# microcontroller.net
KiCad netlist of a schematic drawn in Altium Designer
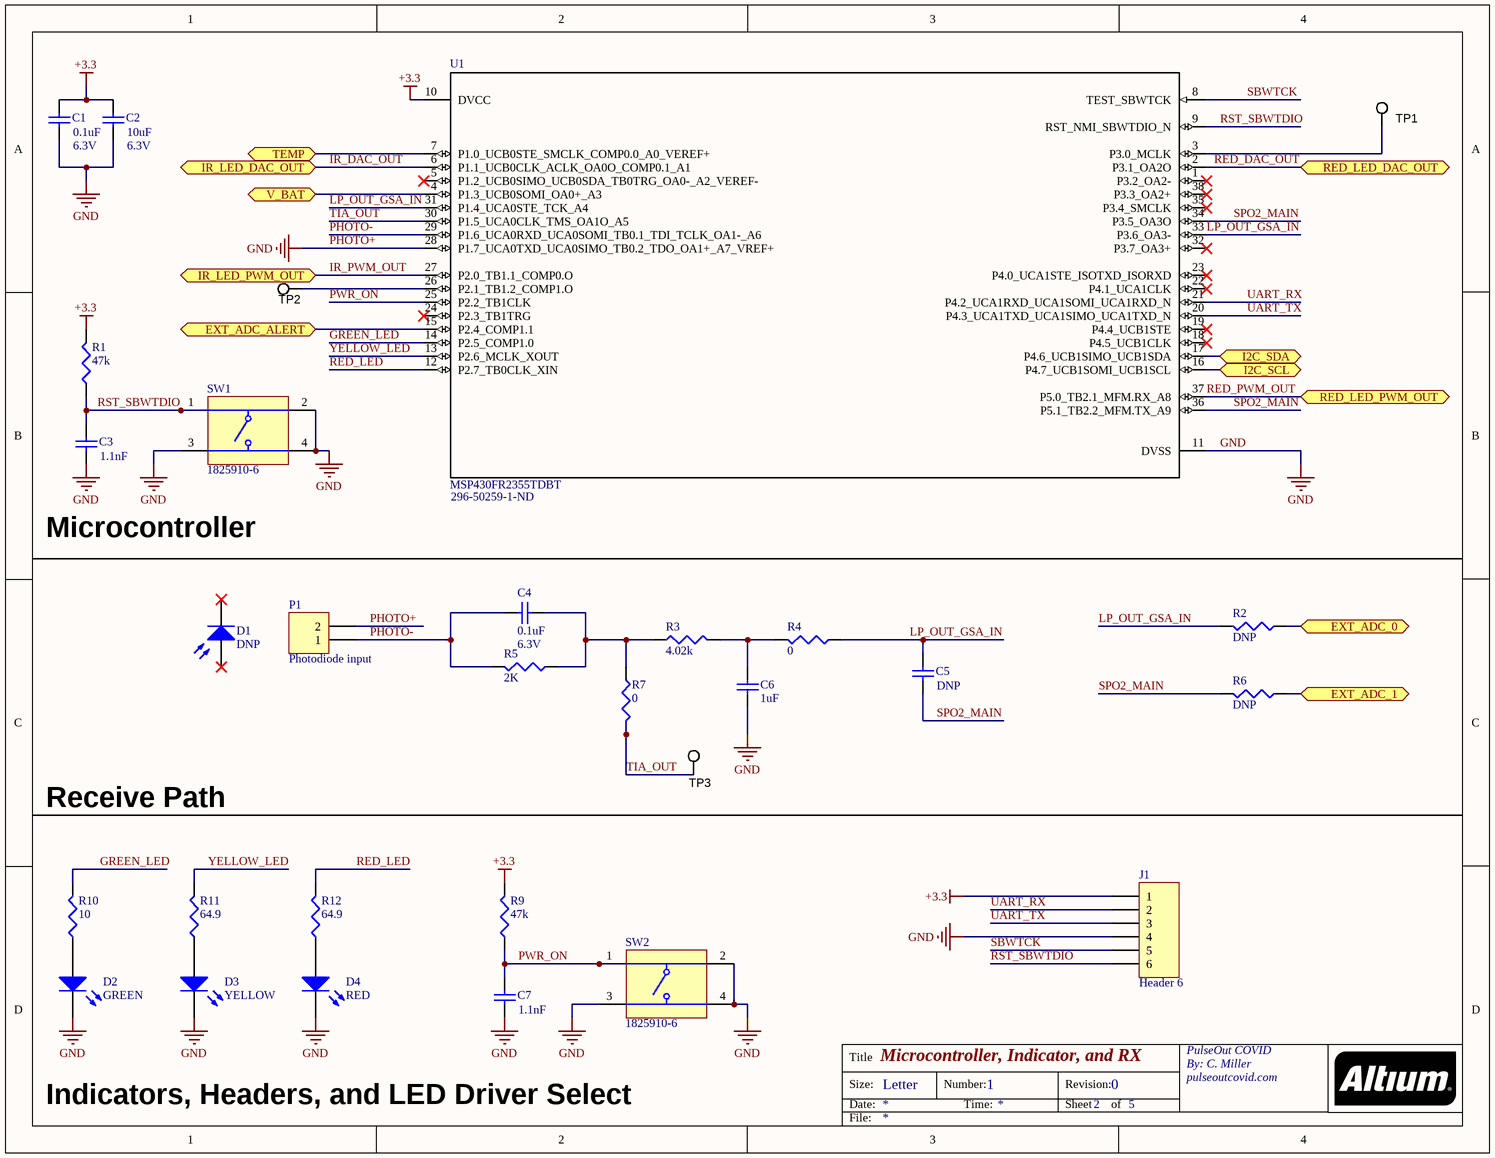
[diagram p0: microcontroller.SchDoc]

(export (version "E")
  (design (tool "Eeschema 10.0.6"))
  (components
    (comp (ref "C1")
      (value "0.1uF")
      (footprint "1608[0603]")
      (description "Capacitor (Semiconductor SIM Model)")
      (fields
        (field (name "VOLTAGE") "6.3V")
        (field (name "MPN") "06036C104KAT4A")
        (field (name "MANUFACTURER") "AVX Corporation")
        (field (name "PUBLISHER") "Altium Limited")
      )
      (libsource (lib "Miscellaneous Devices") (part "Cap Semi"))
    )
    (comp (ref "C2")
      (value "10uF")
      (footprint "1608[0603]")
      (description "Capacitor (Semiconductor SIM Model)")
      (fields
        (field (name "VOLTAGE") "6.3V")
        (field (name "MPN") "JMK107ABJ106KA-T")
        (field (name "MANUFACTURER") "Taiyo Yuden")
        (field (name "PUBLISHER") "Altium Limited")
      )
      (libsource (lib "Miscellaneous Devices") (part "Cap Semi"))
    )
    (comp (ref "C3")
      (value "1.1nF")
      (footprint "0603")
      (description "Capacitor (Semiconductor SIM Model)")
      (fields
        (field (name "MPN") "GRM1885C1H112JA01D")
        (field (name "MANUFACTURER") "Murata Electronics")
        (field (name "PUBLISHER") "Altium Limited")
      )
      (libsource (lib "Miscellaneous Devices") (part "Cap Semi"))
    )
    (comp (ref "C4")
      (value "0.1uF")
      (footprint "1608[0603]")
      (description "Capacitor (Semiconductor SIM Model)")
      (fields
        (field (name "VOLTAGE") "6.3V")
        (field (name "MPN") "06036C104KAT4A")
        (field (name "MANUFACTURER") "AVX Corporation")
        (field (name "PUBLISHER") "Altium Limited")
      )
      (libsource (lib "Miscellaneous Devices") (part "Cap Semi"))
    )
    (comp (ref "C5")
      (value "DNP")
      (footprint "0603")
      (description "Capacitor (Semiconductor SIM Model)")
      (fields (field (name "Comment") "Cap Semi") (field (name "PUBLISHER") "Altium Limited"))
      (libsource (lib "Miscellaneous Devices") (part "Cap Semi"))
    )
    (comp (ref "C6")
      (value "1uF")
      (footprint "1608[0603]")
      (description "Capacitor (Semiconductor SIM Model)")
      (fields
        (field (name "MPN") "C0603X105J9RAC7867")
        (field (name "MANUFACTURER") "KEMET")
        (field (name "PUBLISHER") "Altium Limited")
      )
      (libsource (lib "Miscellaneous Devices") (part "Cap Semi"))
    )
    (comp (ref "C7")
      (value "1.1nF")
      (footprint "0603")
      (description "Capacitor (Semiconductor SIM Model)")
      (fields
        (field (name "MPN") "GRM1885C1H112JA01D")
        (field (name "MANUFACTURER") "Murata Electronics")
        (field (name "PUBLISHER") "Altium Limited")
      )
      (libsource (lib "Miscellaneous Devices") (part "Cap Semi"))
    )
    (comp (ref "D1")
      (value "DNP")
      (footprint "PIN2")
      (description "Photosensitive Diode")
      (fields
        (field (name "MPN") "BPW34")
        (field (name "MANUFACTURER") "OSRAM Opto Semiconductors Inc.")
        (field (name "PUBLISHER") "Altium Limited")
      )
      (libsource (lib "Miscellaneous Devices") (part "Photo Sen"))
    )
    (comp (ref "D2")
      (value "GREEN")
      (footprint "3.5X2.8X1.9")
      (description "Typical BLUE SiC LED")
      (fields
        (field (name "MPN") "150141GS73100")
        (field (name "MANUFACTURER") "Wurth Elektronik")
        (field (name "PUBLISHER") "Altium Limited")
      )
      (libsource (lib "Miscellaneous Devices") (part "LED3"))
    )
    (comp (ref "D3")
      (value "YELLOW")
      (footprint "3.5X2.8X1.9")
      (description "Typical BLUE SiC LED")
      (fields
        (field (name "MPN") "SML-Z14YTT86C")
        (field (name "MANUFACTURER") "Rohm Semiconductor")
        (field (name "PUBLISHER") "Altium Limited")
      )
      (libsource (lib "Miscellaneous Devices") (part "LED3"))
    )
    (comp (ref "D4")
      (value "RED")
      (footprint "3.5X2.8X1.9")
      (description "Typical BLUE SiC LED")
      (fields
        (field (name "MPN") "150141RS73100")
        (field (name "MANUFACTURER") "Wurth Elektronik")
        (field (name "PUBLISHER") "Altium Limited")
      )
      (libsource (lib "Miscellaneous Devices") (part "LED3"))
    )
    (comp (ref "J1")
      (value "Header 6")
      (footprint "HDR1X6")
      (description "Header, 6-Pin")
      (fields
        (field (name "MPN") "800-10-006-10-001000")
        (field (name "MANUFACTURER") "Mill-Max Manufacturing")
        (field (name "PUBLISHER") "Altium Limited")
      )
      (libsource (lib "Miscellaneous Connectors") (part "Header 6"))
    )
    (comp (ref "P1")
      (value "Photodiode input")
      (footprint "HDR1X2")
      (description "Header, 2-Pin")
      (fields (field (name "PUBLISHER") "Altium Limited"))
      (libsource (lib "Miscellaneous Connectors") (part "Header 2"))
    )
    (comp (ref "R1")
      (value "47k")
      (footprint "J1-0603")
      (description "Resistor")
      (fields
        (field (name "MPN") "RC0603JR-0747KL")
        (field (name "MANUFACTURER") "Yageo")
        (field (name "PUBLISHER") "Altium Limited")
      )
      (libsource (lib "Miscellaneous Devices") (part "Res3"))
    )
    (comp (ref "R2")
      (value "DNP")
      (footprint "J1-0603")
      (description "Resistor")
      (fields (field (name "Comment") "Res3") (field (name "PUBLISHER") "Altium Limited"))
      (libsource (lib "Miscellaneous Devices") (part "Res3"))
    )
    (comp (ref "R3")
      (value "4.02k")
      (footprint "J1-0603")
      (description "Resistor")
      (fields
        (field (name "MPN") "RMCF0603FT4K02")
        (field (name "MANUFACTURER") "Stackpole Electronics")
        (field (name "PUBLISHER") "Altium Limited")
      )
      (libsource (lib "Miscellaneous Devices") (part "Res3"))
    )
    (comp (ref "R4")
      (value "0")
      (footprint "J1-0603")
      (description "Resistor")
      (fields
        (field (name "MPN") "RC0603JR-070RL")
        (field (name "MANUFACTURER") "Yageo")
        (field (name "PUBLISHER") "Altium Limited")
      )
      (libsource (lib "Miscellaneous Devices") (part "Res3"))
    )
    (comp (ref "R5")
      (value "2K")
      (footprint "J1-0603")
      (description "Resistor")
      (fields
        (field (name "MPN") "RC0603FR-072KL")
        (field (name "MANUFACTURER") "Yageo")
        (field (name "PUBLISHER") "Altium Limited")
      )
      (libsource (lib "Miscellaneous Devices") (part "Res3"))
    )
    (comp (ref "R6")
      (value "DNP")
      (footprint "J1-0603")
      (description "Resistor")
      (fields (field (name "Comment") "Res3") (field (name "PUBLISHER") "Altium Limited"))
      (libsource (lib "Miscellaneous Devices") (part "Res3"))
    )
    (comp (ref "R7")
      (value "0")
      (footprint "J1-0603")
      (description "Resistor")
      (fields
        (field (name "MPN") "RC0603JR-070RL")
        (field (name "MANUFACTURER") "Yageo")
        (field (name "PUBLISHER") "Altium Limited")
      )
      (libsource (lib "Miscellaneous Devices") (part "Res3"))
    )
    (comp (ref "R9")
      (value "47k")
      (footprint "J1-0603")
      (description "Resistor")
      (fields
        (field (name "MPN") "RC0603JR-0747KL")
        (field (name "MANUFACTURER") "Yageo")
        (field (name "PUBLISHER") "Altium Limited")
      )
      (libsource (lib "Miscellaneous Devices") (part "Res3"))
    )
    (comp (ref "R10")
      (value "10")
      (footprint "J1-0603")
      (description "Resistor")
      (fields
        (field (name "MPN") "RC0603FR-0710RL")
        (field (name "MANUFACTURER") "Yageo")
        (field (name "PUBLISHER") "Altium Limited")
      )
      (libsource (lib "Miscellaneous Devices") (part "Res3"))
    )
    (comp (ref "R11")
      (value "64.9")
      (footprint "J1-0603")
      (description "Resistor")
      (fields
        (field (name "MPN") "ERA-3AEB64R9V")
        (field (name "MANUFACTURER") "Panasonic")
        (field (name "PUBLISHER") "Altium Limited")
      )
      (libsource (lib "Miscellaneous Devices") (part "Res3"))
    )
    (comp (ref "R12")
      (value "64.9")
      (footprint "J1-0603")
      (description "Resistor")
      (fields
        (field (name "MPN") "ERA-3AEB64R9V")
        (field (name "MANUFACTURER") "Panasonic")
        (field (name "PUBLISHER") "Altium Limited")
      )
      (libsource (lib "Miscellaneous Devices") (part "Res3"))
    )
    (comp (ref "SW1")
      (value "1825910-6")
      (footprint "TECO-1825910-6_V")
      (description "Tact Switch, SPST-NO, 0.05 A, -35 to 85 degC, 4-Pin THD, RoHS, Bulk")
      (fields (field (name "MANUFACTURER") "TE Connectivity"))
      (libsource (lib "Altium Content Vault") (part "SW-SPST-4_A"))
    )
    (comp (ref "SW2")
      (value "1825910-6")
      (footprint "TECO-1825910-6_V")
      (description "Tact Switch, SPST-NO, 0.05 A, -35 to 85 degC, 4-Pin THD, RoHS, Bulk")
      (fields (field (name "MANUFACTURER") "TE Connectivity"))
      (libsource (lib "Altium Content Vault") (part "SW-SPST-4_A"))
    )
    (comp (ref "TP1")
      (value "5002")
      (footprint "Keystone5002")
      (description "Test Point, Miniature, White, TH")
      (fields (field (name "MANUFACTURER") "Keystone") (field (name "PUBLISHER") "Texas Instruments"))
      (libsource (lib "MDBU017A") (part "5002"))
    )
    (comp (ref "TP2")
      (value "5002")
      (footprint "Keystone5002")
      (description "Test Point, Miniature, White, TH")
      (fields (field (name "MANUFACTURER") "Keystone") (field (name "PUBLISHER") "Texas Instruments"))
      (libsource (lib "MDBU017A") (part "5002"))
    )
    (comp (ref "TP3")
      (value "5002")
      (footprint "Keystone5002")
      (description "Test Point, Miniature, White, TH")
      (fields (field (name "MANUFACTURER") "Keystone") (field (name "PUBLISHER") "Texas Instruments"))
      (libsource (lib "MDBU017A") (part "5002"))
    )
    (comp (ref "U1")
      (value "MSP430FR2355TDBT")
      (footprint "DBT0038A_N")
      (description "MSP430 IC")
      (fields
        (field (name "MANUFACTURER") "Texas Instruments")
        (field (name "PARTNUMBER") "MSP430FR2355IDBT")
        (field (name "DIGIKEY") "296-50259-1-ND")
        (field (name "COPYRIGHT") "Copyright (C) 2018 Accelerated Designs. All rights reserved")
      )
      (libsource (lib "CustomLib") (part "MSP430FR2355TDBT"))
    )
  )
  (nets
    (net (code "1") (name "+3.3") (class "Default")
      (node (ref "C1") (pin "2") (pinfunction "2_2") (pintype "passive"))
      (node (ref "C2") (pin "2") (pinfunction "2_2") (pintype "passive"))
      (node (ref "J1") (pin "1") (pinfunction "1_1") (pintype "passive"))
      (node (ref "R1") (pin "2") (pinfunction "2_2") (pintype "passive"))
      (node (ref "R9") (pin "2") (pinfunction "2_2") (pintype "passive"))
      (node (ref "U1") (pin "10") (pinfunction "DVCC_10") (pintype "power_in"))
    )
    (net (code "2") (name "/EXT_ADC_0") (class "Default")
      (node (ref "R2") (pin "1") (pinfunction "1_1") (pintype "passive"))
    )
    (net (code "3") (name "/EXT_ADC_1") (class "Default")
      (node (ref "R6") (pin "1") (pinfunction "1_1") (pintype "passive"))
    )
    (net (code "4") (name "/EXT_ADC_ALERT") (class "Default")
      (node (ref "U1") (pin "15") (pinfunction "P2.4_COMP1.1_15") (pintype "bidirectional"))
    )
    (net (code "5") (name "/GREEN_LED") (class "Default")
      (node (ref "R10") (pin "2") (pinfunction "2_2") (pintype "passive"))
      (node (ref "U1") (pin "14") (pinfunction "P2.5_COMP1.0_14") (pintype "bidirectional"))
    )
    (net (code "6") (name "/I2C_SCL") (class "Default")
      (node (ref "U1") (pin "16") (pinfunction "P4.7_UCB1SOMI_UCB1SCL_16") (pintype "bidirectional"))
    )
    (net (code "7") (name "/I2C_SDA") (class "Default")
      (node (ref "U1") (pin "17") (pinfunction "P4.6_UCB1SIMO_UCB1SDA_17") (pintype "bidirectional"))
    )
    (net (code "8") (name "/IR_DAC_OUT") (class "Default")
      (node (ref "U1") (pin "6") (pinfunction "P1.1_UCB0CLK_ACLK_OA0O_COMP0.1_A1_6") (pintype "bidirectional"))
    )
    (net (code "9") (name "/IR_PWM_OUT") (class "Default")
      (node (ref "U1") (pin "27") (pinfunction "P2.0_TB1.1_COMP0.O_27") (pintype "bidirectional"))
    )
    (net (code "10") (name "/LP_OUT_GSA_IN") (class "Default")
      (node (ref "C5") (pin "2") (pinfunction "2_2") (pintype "passive"))
      (node (ref "R2") (pin "2") (pinfunction "2_2") (pintype "passive"))
      (node (ref "R4") (pin "1") (pinfunction "1_1") (pintype "passive"))
      (node (ref "U1") (pin "31") (pinfunction "P1.4_UCA0STE_TCK_A4_31") (pintype "bidirectional"))
      (node (ref "U1") (pin "33") (pinfunction "P3.6_OA3-_33") (pintype "bidirectional"))
    )
    (net (code "11") (name "/PHOTO-") (class "Default")
      (node (ref "C4") (pin "2") (pinfunction "2_2") (pintype "passive"))
      (node (ref "P1") (pin "1") (pinfunction "1_1") (pintype "passive"))
      (node (ref "R5") (pin "2") (pinfunction "2_2") (pintype "passive"))
      (node (ref "U1") (pin "29") (pinfunction "P1.6_UCA0RXD_UCA0SOMI_TB0.1_TDI_TCLK_OA1-_A6_29") (pintype "bidirectional"))
    )
    (net (code "12") (name "/PWR_ON") (class "Default")
      (node (ref "C7") (pin "2") (pinfunction "2_2") (pintype "passive"))
      (node (ref "R9") (pin "1") (pinfunction "1_1") (pintype "passive"))
      (node (ref "SW2") (pin "1") (pinfunction "1_1") (pintype "passive"))
      (node (ref "U1") (pin "25") (pinfunction "P2.2_TB1CLK_25") (pintype "bidirectional"))
    )
    (net (code "13") (name "/RED_DAC_OUT") (class "Default")
      (node (ref "U1") (pin "2") (pinfunction "P3.1_OA2O_2") (pintype "bidirectional"))
    )
    (net (code "14") (name "/RED_LED") (class "Default")
      (node (ref "R12") (pin "2") (pinfunction "2_2") (pintype "passive"))
      (node (ref "U1") (pin "12") (pinfunction "P2.7_TB0CLK_XIN_12") (pintype "bidirectional"))
    )
    (net (code "15") (name "/RED_PWM_OUT") (class "Default")
      (node (ref "U1") (pin "37") (pinfunction "P5.0_TB2.1_MFM.RX_A8_37") (pintype "bidirectional"))
    )
    (net (code "16") (name "/RST_SBWTDIO") (class "Default")
      (node (ref "C3") (pin "2") (pinfunction "2_2") (pintype "passive"))
      (node (ref "J1") (pin "6") (pinfunction "6_6") (pintype "passive"))
      (node (ref "R1") (pin "1") (pinfunction "1_1") (pintype "passive"))
      (node (ref "SW1") (pin "1") (pinfunction "1_1") (pintype "passive"))
      (node (ref "U1") (pin "9") (pinfunction "RST_NMI_SBWTDIO_N_9") (pintype "bidirectional"))
    )
    (net (code "17") (name "/SBWTCK") (class "Default")
      (node (ref "J1") (pin "5") (pinfunction "5_5") (pintype "passive"))
      (node (ref "U1") (pin "8") (pinfunction "TEST_SBWTCK_8") (pintype "input"))
    )
    (net (code "18") (name "/SPO2_MAIN") (class "Default")
      (node (ref "C5") (pin "1") (pinfunction "1_1") (pintype "passive"))
      (node (ref "R6") (pin "2") (pinfunction "2_2") (pintype "passive"))
      (node (ref "U1") (pin "34") (pinfunction "P3.5_OA3O_34") (pintype "bidirectional"))
      (node (ref "U1") (pin "36") (pinfunction "P5.1_TB2.2_MFM.TX_A9_36") (pintype "bidirectional"))
    )
    (net (code "19") (name "/TEMP") (class "Default")
      (node (ref "U1") (pin "7") (pinfunction "P1.0_UCB0STE_SMCLK_COMP0.0_A0_VEREF+_7") (pintype "bidirectional"))
    )
    (net (code "20") (name "/TIA_OUT") (class "Default")
      (node (ref "R7") (pin "2") (pinfunction "2_2") (pintype "passive"))
      (node (ref "TP3") (pin "1") (pintype "passive"))
      (node (ref "U1") (pin "30") (pinfunction "P1.5_UCA0CLK_TMS_OA1O_A5_30") (pintype "bidirectional"))
    )
    (net (code "21") (name "/UART_RX") (class "Default")
      (node (ref "J1") (pin "2") (pinfunction "2_2") (pintype "passive"))
      (node (ref "U1") (pin "21") (pinfunction "P4.2_UCA1RXD_UCA1SOMI_UCA1RXD_N_21") (pintype "bidirectional"))
    )
    (net (code "22") (name "/UART_TX") (class "Default")
      (node (ref "J1") (pin "3") (pinfunction "3_3") (pintype "passive"))
      (node (ref "U1") (pin "20") (pinfunction "P4.3_UCA1TXD_UCA1SIMO_UCA1TXD_N_20") (pintype "bidirectional"))
    )
    (net (code "23") (name "/V_BAT") (class "Default")
      (node (ref "U1") (pin "4") (pinfunction "P1.3_UCB0SOMI_OA0+_A3_4") (pintype "bidirectional"))
    )
    (net (code "24") (name "/YELLOW_LED") (class "Default")
      (node (ref "R11") (pin "2") (pinfunction "2_2") (pintype "passive"))
      (node (ref "U1") (pin "13") (pinfunction "P2.6_MCLK_XOUT_13") (pintype "bidirectional"))
    )
    (net (code "25") (name "GND") (class "Default")
      (node (ref "C1") (pin "1") (pinfunction "1_1") (pintype "passive"))
      (node (ref "C2") (pin "1") (pinfunction "1_1") (pintype "passive"))
      (node (ref "C3") (pin "1") (pinfunction "1_1") (pintype "passive"))
      (node (ref "C6") (pin "2") (pinfunction "2_2") (pintype "passive"))
      (node (ref "C7") (pin "1") (pinfunction "1_1") (pintype "passive"))
      (node (ref "D2") (pin "2") (pinfunction "K_2") (pintype "passive"))
      (node (ref "D3") (pin "2") (pinfunction "K_2") (pintype "passive"))
      (node (ref "D4") (pin "2") (pinfunction "K_2") (pintype "passive"))
      (node (ref "J1") (pin "4") (pinfunction "4_4") (pintype "passive"))
      (node (ref "P1") (pin "2") (pinfunction "2_2") (pintype "passive"))
      (node (ref "SW1") (pin "2") (pinfunction "2_2") (pintype "passive"))
      (node (ref "SW1") (pin "3") (pinfunction "3_3") (pintype "passive"))
      (node (ref "SW1") (pin "4") (pinfunction "4_4") (pintype "passive"))
      (node (ref "SW2") (pin "2") (pinfunction "2_2") (pintype "passive"))
      (node (ref "SW2") (pin "3") (pinfunction "3_3") (pintype "passive"))
      (node (ref "SW2") (pin "4") (pinfunction "4_4") (pintype "passive"))
      (node (ref "U1") (pin "11") (pinfunction "DVSS_11") (pintype "power_in"))
      (node (ref "U1") (pin "28") (pinfunction "P1.7_UCA0TXD_UCA0SIMO_TB0.2_TDO_OA1+_A7_VREF+_28") (pintype "bidirectional"))
    )
    (net (code "26") (name "Net-(C4-Pad1)") (class "Default")
      (node (ref "C4") (pin "1") (pinfunction "1_1") (pintype "passive"))
      (node (ref "R3") (pin "1") (pinfunction "1_1") (pintype "passive"))
      (node (ref "R5") (pin "1") (pinfunction "1_1") (pintype "passive"))
      (node (ref "R7") (pin "1") (pinfunction "1_1") (pintype "passive"))
    )
    (net (code "27") (name "Net-(C6-Pad1)") (class "Default")
      (node (ref "C6") (pin "1") (pinfunction "1_1") (pintype "passive"))
      (node (ref "R3") (pin "2") (pinfunction "2_2") (pintype "passive"))
      (node (ref "R4") (pin "2") (pinfunction "2_2") (pintype "passive"))
    )
    (net (code "28") (name "Net-(D2-A)") (class "Default")
      (node (ref "D2") (pin "1") (pinfunction "A_1") (pintype "passive"))
      (node (ref "R10") (pin "1") (pinfunction "1_1") (pintype "passive"))
    )
    (net (code "29") (name "Net-(D3-A)") (class "Default")
      (node (ref "D3") (pin "1") (pinfunction "A_1") (pintype "passive"))
      (node (ref "R11") (pin "1") (pinfunction "1_1") (pintype "passive"))
    )
    (net (code "30") (name "Net-(D4-A)") (class "Default")
      (node (ref "D4") (pin "1") (pinfunction "A_1") (pintype "passive"))
      (node (ref "R12") (pin "1") (pinfunction "1_1") (pintype "passive"))
    )
    (net (code "31") (name "Net-(U1-P2.1_TB1.2_COMP1.O)") (class "Default")
      (node (ref "TP2") (pin "1") (pintype "passive"))
      (node (ref "U1") (pin "26") (pinfunction "P2.1_TB1.2_COMP1.O_26") (pintype "bidirectional"))
    )
    (net (code "32") (name "Net-(U1-P3.0_MCLK)") (class "Default")
      (node (ref "TP1") (pin "1") (pintype "passive"))
      (node (ref "U1") (pin "3") (pinfunction "P3.0_MCLK_3") (pintype "bidirectional"))
    )
    (net (code "33") (name "unconnected-(D1-A-Pad1)") (class "Default")
      (node (ref "D1") (pin "1") (pinfunction "A_1") (pintype "passive+no_connect"))
    )
    (net (code "34") (name "unconnected-(D1-K-Pad2)") (class "Default")
      (node (ref "D1") (pin "2") (pinfunction "K_2") (pintype "passive+no_connect"))
    )
    (net (code "35") (name "unconnected-(U1-P1.2_UCB0SIMO_UCB0SDA_TB0TRG_OA0-_A2_VEREF--Pad5)") (class "Default")
      (node (ref "U1") (pin "5") (pinfunction "P1.2_UCB0SIMO_UCB0SDA_TB0TRG_OA0-_A2_VEREF-_5") (pintype "bidirectional+no_connect"))
    )
    (net (code "36") (name "unconnected-(U1-P2.3_TB1TRG-Pad24)") (class "Default")
      (node (ref "U1") (pin "24") (pinfunction "P2.3_TB1TRG_24") (pintype "bidirectional+no_connect"))
    )
    (net (code "37") (name "unconnected-(U1-P3.2_OA2--Pad1)") (class "Default")
      (node (ref "U1") (pin "1") (pinfunction "P3.2_OA2-_1") (pintype "bidirectional+no_connect"))
    )
    (net (code "38") (name "unconnected-(U1-P3.3_OA2+-Pad38)") (class "Default")
      (node (ref "U1") (pin "38") (pinfunction "P3.3_OA2+_38") (pintype "bidirectional+no_connect"))
    )
    (net (code "39") (name "unconnected-(U1-P3.4_SMCLK-Pad35)") (class "Default")
      (node (ref "U1") (pin "35") (pinfunction "P3.4_SMCLK_35") (pintype "bidirectional+no_connect"))
    )
    (net (code "40") (name "unconnected-(U1-P3.7_OA3+-Pad32)") (class "Default")
      (node (ref "U1") (pin "32") (pinfunction "P3.7_OA3+_32") (pintype "bidirectional+no_connect"))
    )
    (net (code "41") (name "unconnected-(U1-P4.0_UCA1STE_ISOTXD_ISORXD-Pad23)") (class "Default")
      (node (ref "U1") (pin "23") (pinfunction "P4.0_UCA1STE_ISOTXD_ISORXD_23") (pintype "bidirectional+no_connect"))
    )
    (net (code "42") (name "unconnected-(U1-P4.1_UCA1CLK-Pad22)") (class "Default")
      (node (ref "U1") (pin "22") (pinfunction "P4.1_UCA1CLK_22") (pintype "bidirectional+no_connect"))
    )
    (net (code "43") (name "unconnected-(U1-P4.4_UCB1STE-Pad19)") (class "Default")
      (node (ref "U1") (pin "19") (pinfunction "P4.4_UCB1STE_19") (pintype "bidirectional+no_connect"))
    )
    (net (code "44") (name "unconnected-(U1-P4.5_UCB1CLK-Pad18)") (class "Default")
      (node (ref "U1") (pin "18") (pinfunction "P4.5_UCB1CLK_18") (pintype "bidirectional+no_connect"))
    )
  )
)
